# channelSelctorDriver.net
KiCad netlist of a schematic drawn in EAGLE
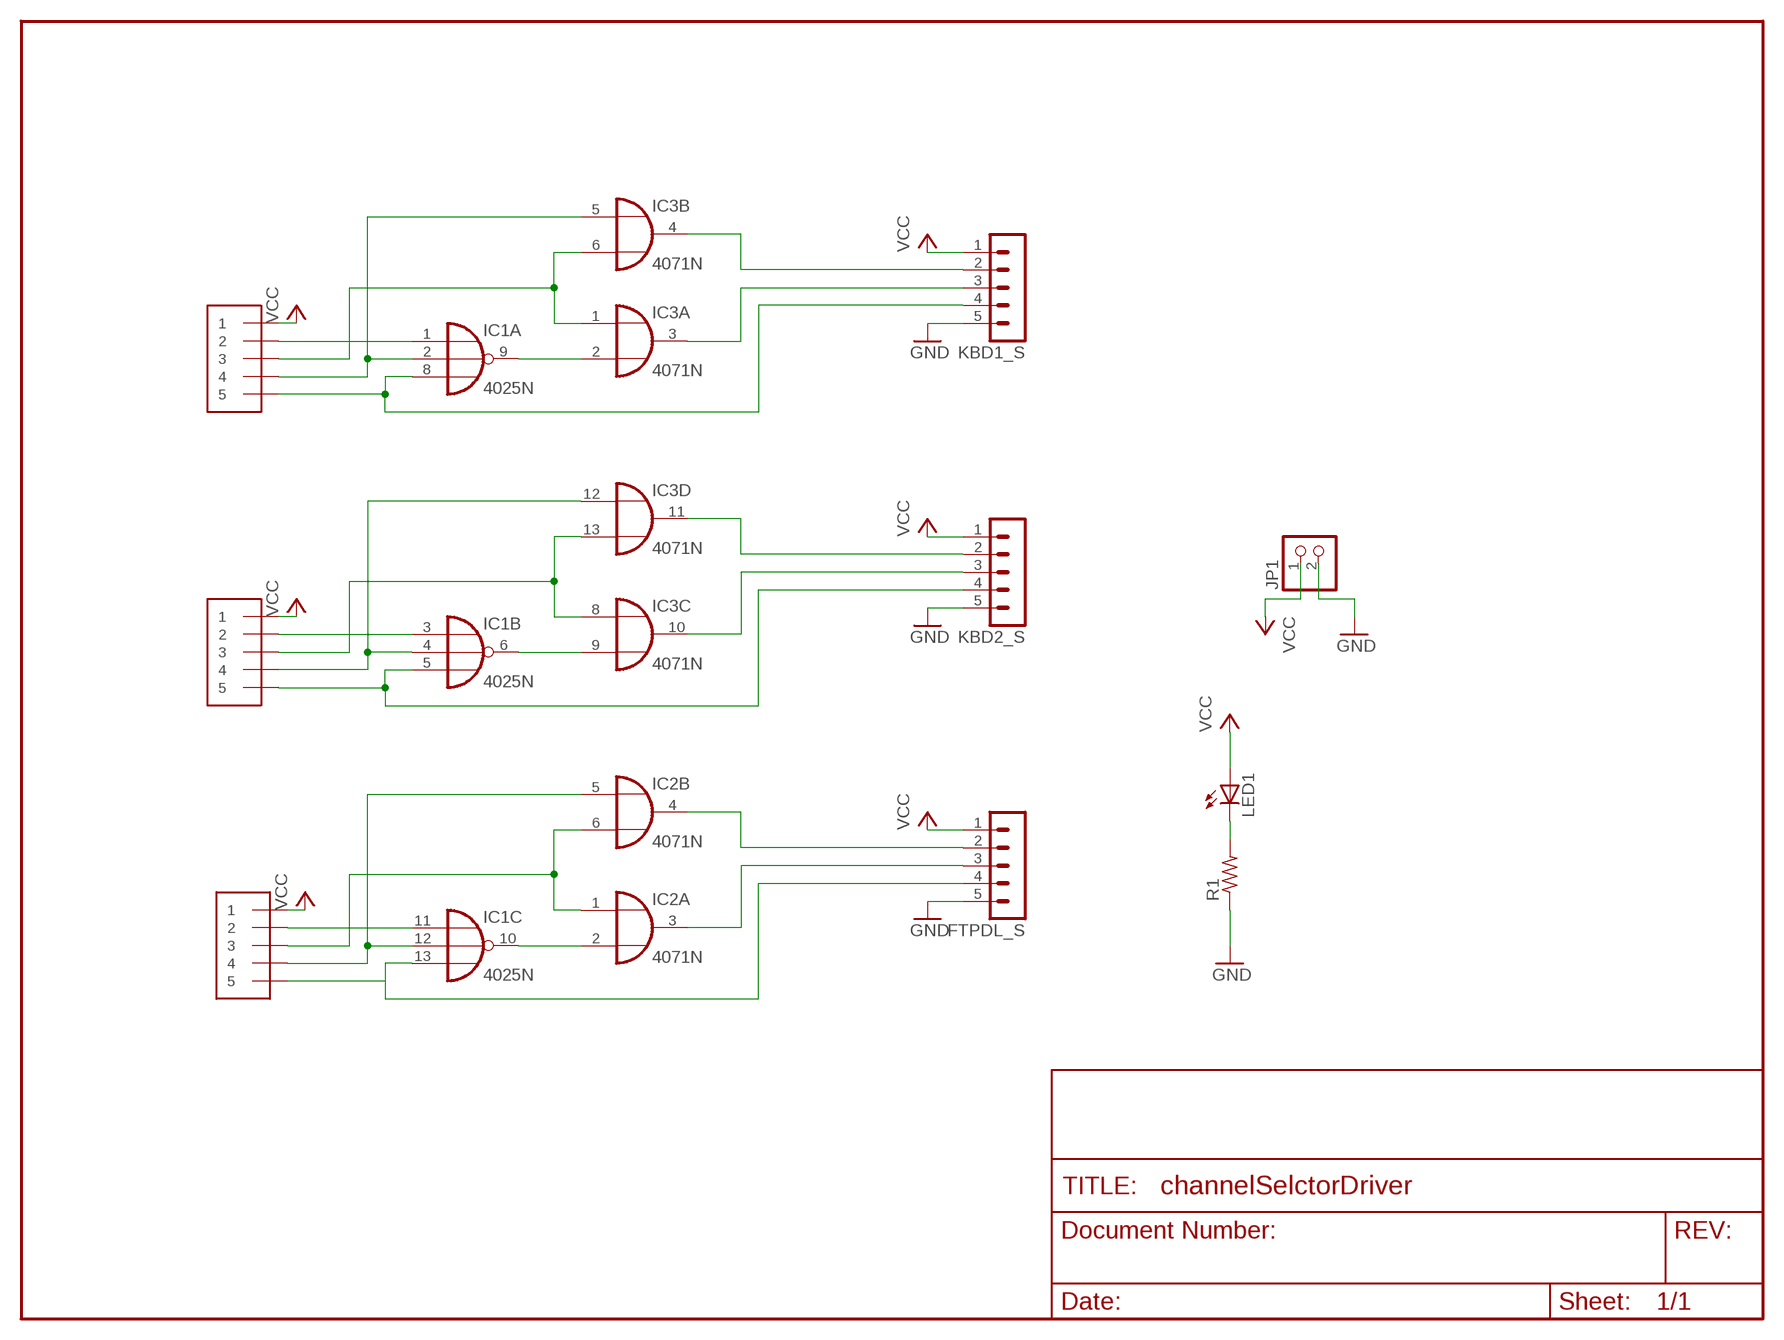
[diagram p0: schematic, sheet 1]

(export (version "E")
  (design (tool "Eeschema 10.0.6"))
  (components
    (comp (ref "FTPDL_S")
      (value "MA05-1")
      (footprint "eagle-import:MA05-1")
      (libsource (lib "eagle-import") (part "MA05-1"))
    )
    (comp (ref "IC1")
      (value "4025N")
      (footprint "eagle-import:DIL14")
      (libsource (lib "eagle-import") (part "4025N"))
    )
    (comp (ref "IC2")
      (value "4071N")
      (footprint "eagle-import:DIL14")
      (libsource (lib "eagle-import") (part "4071N"))
    )
    (comp (ref "IC3")
      (value "4071N")
      (footprint "eagle-import:DIL14")
      (libsource (lib "eagle-import") (part "4071N"))
    )
    (comp (ref "JP1")
      (value "PINHD-1X2")
      (footprint "eagle-import:1X02")
      (libsource (lib "eagle-import") (part "PINHD-1X2"))
    )
    (comp (ref "KBD1_C")
      (value "1X5")
      (footprint "eagle-import:1X05-3.5MM")
      (libsource (lib "eagle-import") (part "1X5"))
    )
    (comp (ref "KBD1_S")
      (value "MA05-1")
      (footprint "eagle-import:MA05-1")
      (libsource (lib "eagle-import") (part "MA05-1"))
    )
    (comp (ref "KBD2_C")
      (value "1X5")
      (footprint "eagle-import:1X05-3.5MM")
      (libsource (lib "eagle-import") (part "1X5"))
    )
    (comp (ref "KBD2_S")
      (value "MA05-1")
      (footprint "eagle-import:MA05-1")
      (libsource (lib "eagle-import") (part "MA05-1"))
    )
    (comp (ref "KBD3_C")
      (value "1X5")
      (footprint "eagle-import:1X05-3.5MM")
      (libsource (lib "eagle-import") (part "1X5"))
    )
    (comp (ref "LED1")
      (value "LEDLSU260")
      (footprint "eagle-import:LSU260")
      (libsource (lib "eagle-import") (part "LEDLSU260"))
    )
    (comp (ref "R1")
      (value "R-US_0204/7")
      (footprint "eagle-import:0204_7")
      (libsource (lib "eagle-import") (part "R-US_0204/7"))
    )
  )
  (nets
    (net (code "1") (name "GND") (class "Default")
      (node (ref "FTPDL_S") (pin "5") (pinfunction "5_5") (pintype "passive"))
      (node (ref "JP1") (pin "2") (pinfunction "2_2") (pintype "passive"))
      (node (ref "KBD1_S") (pin "5") (pinfunction "5_5") (pintype "passive"))
      (node (ref "KBD2_S") (pin "5") (pinfunction "5_5") (pintype "passive"))
      (node (ref "R1") (pin "1") (pinfunction "1_1") (pintype "passive"))
    )
    (net (code "2") (name "Net-(IC1A-I0)") (class "Default")
      (node (ref "IC1") (pin "1") (pinfunction "I0_1") (pintype "input"))
      (node (ref "KBD1_C") (pin "2") (pinfunction "2_2") (pintype "passive"))
    )
    (net (code "3") (name "Net-(IC1A-I1)") (class "Default")
      (node (ref "IC1") (pin "2") (pinfunction "I1_2") (pintype "input"))
      (node (ref "IC3") (pin "5") (pinfunction "I0_5") (pintype "input"))
      (node (ref "KBD1_C") (pin "4") (pinfunction "4_4") (pintype "passive"))
    )
    (net (code "4") (name "Net-(IC1A-I2)") (class "Default")
      (node (ref "IC1") (pin "8") (pinfunction "I2_8") (pintype "input"))
      (node (ref "KBD1_C") (pin "5") (pinfunction "5_5") (pintype "passive"))
      (node (ref "KBD1_S") (pin "4") (pinfunction "4_4") (pintype "passive"))
    )
    (net (code "5") (name "Net-(IC1A-O)") (class "Default")
      (node (ref "IC1") (pin "9") (pinfunction "O_9") (pintype "output"))
      (node (ref "IC3") (pin "2") (pinfunction "I1_2") (pintype "input"))
    )
    (net (code "6") (name "Net-(IC1B-I0)") (class "Default")
      (node (ref "IC1") (pin "3") (pinfunction "I0_3") (pintype "input"))
      (node (ref "KBD2_C") (pin "2") (pinfunction "2_2") (pintype "passive"))
    )
    (net (code "7") (name "Net-(IC1B-I1)") (class "Default")
      (node (ref "IC1") (pin "4") (pinfunction "I1_4") (pintype "input"))
      (node (ref "IC3") (pin "12") (pinfunction "I0_12") (pintype "input"))
      (node (ref "KBD2_C") (pin "4") (pinfunction "4_4") (pintype "passive"))
    )
    (net (code "8") (name "Net-(IC1B-I2)") (class "Default")
      (node (ref "IC1") (pin "5") (pinfunction "I2_5") (pintype "input"))
      (node (ref "KBD2_C") (pin "5") (pinfunction "5_5") (pintype "passive"))
      (node (ref "KBD2_S") (pin "4") (pinfunction "4_4") (pintype "passive"))
    )
    (net (code "9") (name "Net-(IC1B-O)") (class "Default")
      (node (ref "IC1") (pin "6") (pinfunction "O_6") (pintype "output"))
      (node (ref "IC3") (pin "9") (pinfunction "I1_9") (pintype "input"))
    )
    (net (code "10") (name "Net-(IC1C-I0)") (class "Default")
      (node (ref "IC1") (pin "11") (pinfunction "I0_11") (pintype "input"))
      (node (ref "KBD3_C") (pin "2") (pinfunction "2_2") (pintype "passive"))
    )
    (net (code "11") (name "Net-(IC1C-I1)") (class "Default")
      (node (ref "IC1") (pin "12") (pinfunction "I1_12") (pintype "input"))
      (node (ref "IC2") (pin "5") (pinfunction "I0_5") (pintype "input"))
      (node (ref "KBD3_C") (pin "4") (pinfunction "4_4") (pintype "passive"))
    )
    (net (code "12") (name "Net-(IC1C-I2)") (class "Default")
      (node (ref "FTPDL_S") (pin "4") (pinfunction "4_4") (pintype "passive"))
      (node (ref "IC1") (pin "13") (pinfunction "I2_13") (pintype "input"))
      (node (ref "KBD3_C") (pin "5") (pinfunction "5_5") (pintype "passive"))
    )
    (net (code "13") (name "Net-(IC1C-O)") (class "Default")
      (node (ref "IC1") (pin "10") (pinfunction "O_10") (pintype "output"))
      (node (ref "IC2") (pin "2") (pinfunction "I1_2") (pintype "input"))
    )
    (net (code "14") (name "Net-(IC2A-I0)") (class "Default")
      (node (ref "IC2") (pin "1") (pinfunction "I0_1") (pintype "input"))
      (node (ref "IC2") (pin "6") (pinfunction "I1_6") (pintype "input"))
      (node (ref "KBD3_C") (pin "3") (pinfunction "3_3") (pintype "passive"))
    )
    (net (code "15") (name "Net-(IC2A-O)") (class "Default")
      (node (ref "FTPDL_S") (pin "3") (pinfunction "3_3") (pintype "passive"))
      (node (ref "IC2") (pin "3") (pinfunction "O_3") (pintype "output"))
    )
    (net (code "16") (name "Net-(IC2B-O)") (class "Default")
      (node (ref "FTPDL_S") (pin "2") (pinfunction "2_2") (pintype "passive"))
      (node (ref "IC2") (pin "4") (pinfunction "O_4") (pintype "output"))
    )
    (net (code "17") (name "Net-(IC3A-I0)") (class "Default")
      (node (ref "IC3") (pin "1") (pinfunction "I0_1") (pintype "input"))
      (node (ref "IC3") (pin "6") (pinfunction "I1_6") (pintype "input"))
      (node (ref "KBD1_C") (pin "3") (pinfunction "3_3") (pintype "passive"))
    )
    (net (code "18") (name "Net-(IC3A-O)") (class "Default")
      (node (ref "IC3") (pin "3") (pinfunction "O_3") (pintype "output"))
      (node (ref "KBD1_S") (pin "3") (pinfunction "3_3") (pintype "passive"))
    )
    (net (code "19") (name "Net-(IC3B-O)") (class "Default")
      (node (ref "IC3") (pin "4") (pinfunction "O_4") (pintype "output"))
      (node (ref "KBD1_S") (pin "2") (pinfunction "2_2") (pintype "passive"))
    )
    (net (code "20") (name "Net-(IC3C-I0)") (class "Default")
      (node (ref "IC3") (pin "13") (pinfunction "I1_13") (pintype "input"))
      (node (ref "IC3") (pin "8") (pinfunction "I0_8") (pintype "input"))
      (node (ref "KBD2_C") (pin "3") (pinfunction "3_3") (pintype "passive"))
    )
    (net (code "21") (name "Net-(IC3C-O)") (class "Default")
      (node (ref "IC3") (pin "10") (pinfunction "O_10") (pintype "output"))
      (node (ref "KBD2_S") (pin "3") (pinfunction "3_3") (pintype "passive"))
    )
    (net (code "22") (name "Net-(IC3D-O)") (class "Default")
      (node (ref "IC3") (pin "11") (pinfunction "O_11") (pintype "output"))
      (node (ref "KBD2_S") (pin "2") (pinfunction "2_2") (pintype "passive"))
    )
    (net (code "23") (name "Net-(LED1-C)") (class "Default")
      (node (ref "LED1") (pin "K") (pinfunction "C_K") (pintype "passive"))
      (node (ref "R1") (pin "2") (pinfunction "2_2") (pintype "passive"))
    )
    (net (code "24") (name "VCC") (class "Default")
      (node (ref "FTPDL_S") (pin "1") (pinfunction "1_1") (pintype "passive"))
      (node (ref "JP1") (pin "1") (pinfunction "1_1") (pintype "passive"))
      (node (ref "KBD1_C") (pin "1") (pinfunction "1_1") (pintype "passive"))
      (node (ref "KBD1_S") (pin "1") (pinfunction "1_1") (pintype "passive"))
      (node (ref "KBD2_C") (pin "1") (pinfunction "1_1") (pintype "passive"))
      (node (ref "KBD2_S") (pin "1") (pinfunction "1_1") (pintype "passive"))
      (node (ref "KBD3_C") (pin "1") (pinfunction "1_1") (pintype "passive"))
      (node (ref "LED1") (pin "A") (pinfunction "A_A") (pintype "passive"))
    )
  )
)
